# tick-wifi-mini-mk-1_1.net
KiCad netlist of a schematic drawn in EAGLE
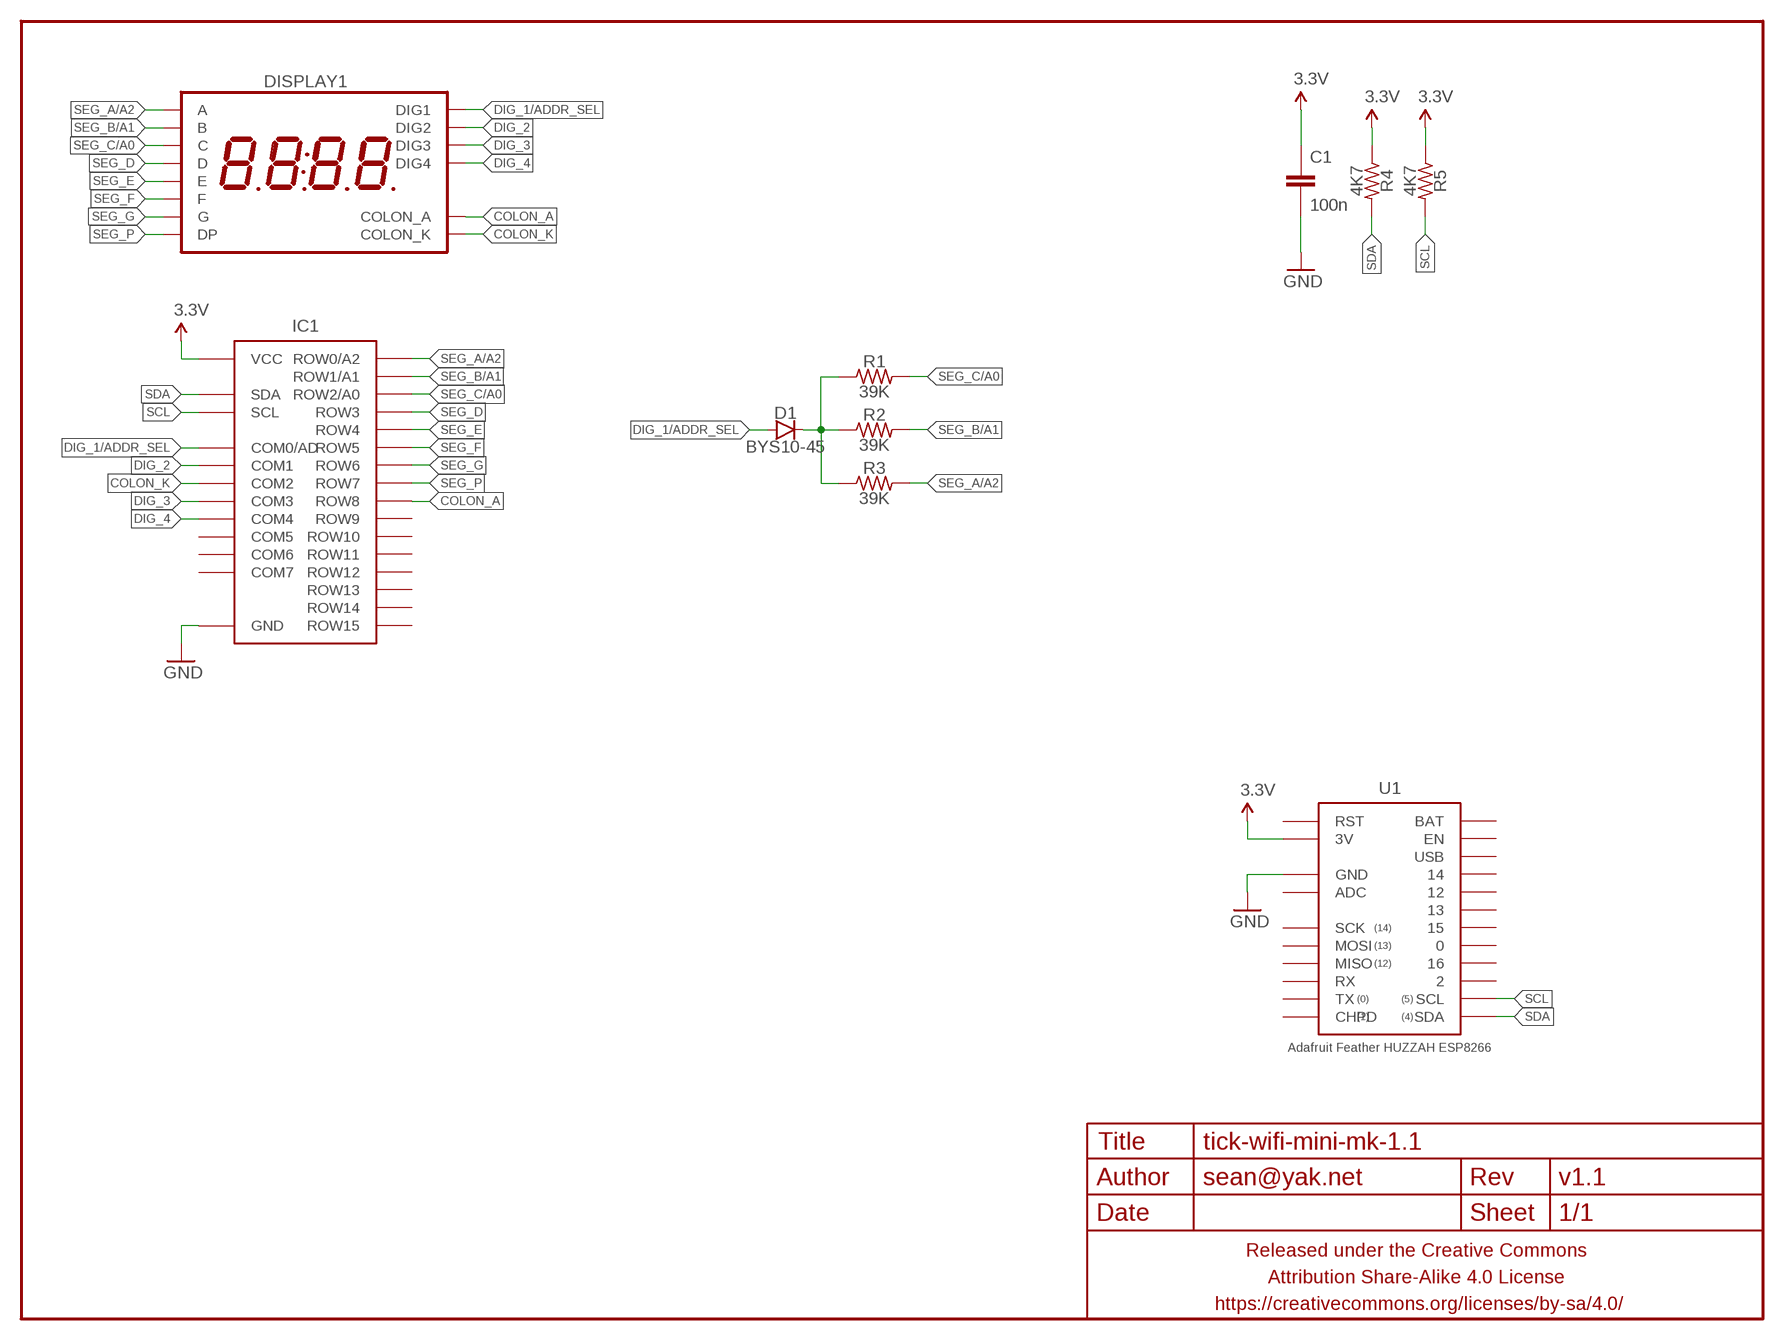
[diagram p0: schematic, sheet 1]

(export (version "E")
  (design (tool "Eeschema 10.0.6"))
  (components
    (comp (ref "C1")
      (value "100n")
      (footprint "eagle-import:C0603")
      (libsource (lib "eagle-import") (part "CAPACITOR-CERAMICC0603"))
    )
    (comp (ref "D1")
      (value "BYS10-45")
      (footprint "eagle-import:SMA-DIODE")
      (libsource (lib "eagle-import") (part "DIODESMA"))
    )
    (comp (ref "DISPLAY1")
      (value "7SEG_4DIGIT_COLON14.2MM-CC")
      (footprint "eagle-import:7SEG_4DIG_0.56IN_14MM_ADAFRUIT")
      (libsource (lib "eagle-import") (part "7SEG_4DIGIT_COLON14.2MM-CC"))
    )
    (comp (ref "FRAME1")
      (value "FRAME-LETTERNO_PACKAGE")
      (footprint "eagle-import:DUMMY")
      (fields (field (name "DESIGNER") "sean@yak.net") (field (name "VERSION") "v1.1"))
      (libsource (lib "eagle-import") (part "FRAME-LETTERNO_PACKAGE"))
    )
    (comp (ref "IC1")
      (value "HT16K33")
      (footprint "eagle-import:SOIC28W")
      (libsource (lib "eagle-import") (part "HT16K33-28SOIC28W"))
    )
    (comp (ref "R1")
      (value "39K")
      (footprint "eagle-import:R0603")
      (libsource (lib "eagle-import") (part "RESISTORR0603"))
    )
    (comp (ref "R2")
      (value "39K")
      (footprint "eagle-import:R0603")
      (libsource (lib "eagle-import") (part "RESISTORR0603"))
    )
    (comp (ref "R3")
      (value "39K")
      (footprint "eagle-import:R0603")
      (libsource (lib "eagle-import") (part "RESISTORR0603"))
    )
    (comp (ref "R4")
      (value "4K7")
      (footprint "eagle-import:R0603")
      (libsource (lib "eagle-import") (part "RESISTORR0603"))
    )
    (comp (ref "R5")
      (value "4K7")
      (footprint "eagle-import:R0603")
      (libsource (lib "eagle-import") (part "RESISTORR0603"))
    )
    (comp (ref "U1")
      (value "Adafruit Feather HUZZAH ESP8266")
      (footprint "eagle-import:ADAFRUIT_FEATHER_HUZZAH_NOSILK")
      (libsource (lib "eagle-import") (part "ADAFRUIT_FEATHER_HUZZAH_ESP8266NOSILK"))
    )
  )
  (nets
    (net (code "1") (name "3.3V") (class "Default")
      (node (ref "C1") (pin "1") (pinfunction "1_1") (pintype "passive"))
      (node (ref "IC1") (pin "28") (pinfunction "VCC_28") (pintype "bidirectional"))
      (node (ref "R4") (pin "1") (pinfunction "1_1") (pintype "passive"))
      (node (ref "R5") (pin "1") (pinfunction "1_1") (pintype "passive"))
      (node (ref "U1") (pin "3V") (pinfunction "3V_3V") (pintype "bidirectional"))
    )
    (net (code "2") (name "COLON_A") (class "Default")
      (node (ref "DISPLAY1") (pin "P$8") (pinfunction "COLON_A_P$8") (pintype "passive"))
      (node (ref "IC1") (pin "17") (pinfunction "ROW8_17") (pintype "bidirectional"))
    )
    (net (code "3") (name "COLON_K") (class "Default")
      (node (ref "DISPLAY1") (pin "P$7") (pinfunction "COLON_K_P$7") (pintype "passive"))
      (node (ref "IC1") (pin "4") (pinfunction "COM2_4") (pintype "bidirectional"))
    )
    (net (code "4") (name "DIG_1{slash}ADDR_SEL") (class "Default")
      (node (ref "D1") (pin "A") (pinfunction "A_A") (pintype "passive"))
      (node (ref "DISPLAY1") (pin "P$14") (pinfunction "DIG1_P$14") (pintype "passive"))
      (node (ref "IC1") (pin "2") (pinfunction "COM0/AD_2") (pintype "bidirectional"))
    )
    (net (code "5") (name "DIG_2") (class "Default")
      (node (ref "DISPLAY1") (pin "P$11") (pinfunction "DIG2_P$11") (pintype "passive"))
      (node (ref "IC1") (pin "3") (pinfunction "COM1_3") (pintype "bidirectional"))
    )
    (net (code "6") (name "DIG_3") (class "Default")
      (node (ref "DISPLAY1") (pin "P$10") (pinfunction "DIG3_P$10") (pintype "passive"))
      (node (ref "IC1") (pin "5") (pinfunction "COM3_5") (pintype "bidirectional"))
    )
    (net (code "7") (name "DIG_4") (class "Default")
      (node (ref "DISPLAY1") (pin "P$6") (pinfunction "DIG4_P$6") (pintype "passive"))
      (node (ref "IC1") (pin "6") (pinfunction "COM4_6") (pintype "bidirectional"))
    )
    (net (code "8") (name "GND") (class "Default")
      (node (ref "C1") (pin "2") (pinfunction "2_2") (pintype "passive"))
      (node (ref "IC1") (pin "1") (pinfunction "GND_1") (pintype "bidirectional"))
      (node (ref "U1") (pin "GND@0") (pinfunction "GND_GND@0") (pintype "bidirectional"))
    )
    (net (code "9") (name "Net-(D1-PadC)") (class "Default")
      (node (ref "D1") (pin "C") (pinfunction "C_C") (pintype "passive"))
      (node (ref "R1") (pin "1") (pinfunction "1_1") (pintype "passive"))
      (node (ref "R2") (pin "1") (pinfunction "1_1") (pintype "passive"))
      (node (ref "R3") (pin "1") (pinfunction "1_1") (pintype "passive"))
    )
    (net (code "10") (name "SCL") (class "Default")
      (node (ref "IC1") (pin "26") (pinfunction "SCL_26") (pintype "bidirectional"))
      (node (ref "R5") (pin "2") (pinfunction "2_2") (pintype "passive"))
      (node (ref "U1") (pin "SCL") (pinfunction "SCL_SCL") (pintype "bidirectional"))
    )
    (net (code "11") (name "SDA") (class "Default")
      (node (ref "IC1") (pin "27") (pinfunction "SDA_27") (pintype "bidirectional"))
      (node (ref "R4") (pin "2") (pinfunction "2_2") (pintype "passive"))
      (node (ref "U1") (pin "SDA") (pinfunction "SDA_SDA") (pintype "bidirectional"))
    )
    (net (code "12") (name "SEG_A{slash}A2") (class "Default")
      (node (ref "DISPLAY1") (pin "P$13") (pinfunction "A_P$13") (pintype "passive"))
      (node (ref "IC1") (pin "25") (pinfunction "ROW0/A2_25") (pintype "bidirectional"))
      (node (ref "R3") (pin "2") (pinfunction "2_2") (pintype "passive"))
    )
    (net (code "13") (name "SEG_B{slash}A1") (class "Default")
      (node (ref "DISPLAY1") (pin "P$9") (pinfunction "B_P$9") (pintype "passive"))
      (node (ref "IC1") (pin "24") (pinfunction "ROW1/A1_24") (pintype "bidirectional"))
      (node (ref "R2") (pin "2") (pinfunction "2_2") (pintype "passive"))
    )
    (net (code "14") (name "SEG_C{slash}A0") (class "Default")
      (node (ref "DISPLAY1") (pin "P$4") (pinfunction "C_P$4") (pintype "passive"))
      (node (ref "IC1") (pin "23") (pinfunction "ROW2/A0_23") (pintype "bidirectional"))
      (node (ref "R1") (pin "2") (pinfunction "2_2") (pintype "passive"))
    )
    (net (code "15") (name "SEG_D") (class "Default")
      (node (ref "DISPLAY1") (pin "P$2") (pinfunction "D_P$2") (pintype "passive"))
      (node (ref "IC1") (pin "22") (pinfunction "ROW3_22") (pintype "bidirectional"))
    )
    (net (code "16") (name "SEG_E") (class "Default")
      (node (ref "DISPLAY1") (pin "P$1") (pinfunction "E_P$1") (pintype "passive"))
      (node (ref "IC1") (pin "21") (pinfunction "ROW4_21") (pintype "bidirectional"))
    )
    (net (code "17") (name "SEG_F") (class "Default")
      (node (ref "DISPLAY1") (pin "P$12") (pinfunction "F_P$12") (pintype "passive"))
      (node (ref "IC1") (pin "20") (pinfunction "ROW5_20") (pintype "bidirectional"))
    )
    (net (code "18") (name "SEG_G") (class "Default")
      (node (ref "DISPLAY1") (pin "P$5") (pinfunction "G_P$5") (pintype "passive"))
      (node (ref "IC1") (pin "19") (pinfunction "ROW6_19") (pintype "bidirectional"))
    )
    (net (code "19") (name "SEG_P") (class "Default")
      (node (ref "DISPLAY1") (pin "P$3") (pinfunction "DP_P$3") (pintype "passive"))
      (node (ref "IC1") (pin "18") (pinfunction "ROW7_18") (pintype "bidirectional"))
    )
    (net (code "20") (name "unconnected-(IC1-COM5-Pad7)") (class "Default")
      (node (ref "IC1") (pin "7") (pinfunction "COM5_7") (pintype "bidirectional"))
    )
    (net (code "21") (name "unconnected-(IC1-COM6-Pad8)") (class "Default")
      (node (ref "IC1") (pin "8") (pinfunction "COM6_8") (pintype "bidirectional"))
    )
    (net (code "22") (name "unconnected-(IC1-COM7-Pad9)") (class "Default")
      (node (ref "IC1") (pin "9") (pinfunction "COM7_9") (pintype "bidirectional"))
    )
    (net (code "23") (name "unconnected-(IC1-ROW9-Pad16)") (class "Default")
      (node (ref "IC1") (pin "16") (pinfunction "ROW9_16") (pintype "bidirectional"))
    )
    (net (code "24") (name "unconnected-(IC1-ROW10-Pad15)") (class "Default")
      (node (ref "IC1") (pin "15") (pinfunction "ROW10_15") (pintype "bidirectional"))
    )
    (net (code "25") (name "unconnected-(IC1-ROW11-Pad14)") (class "Default")
      (node (ref "IC1") (pin "14") (pinfunction "ROW11_14") (pintype "bidirectional"))
    )
    (net (code "26") (name "unconnected-(IC1-ROW12-Pad13)") (class "Default")
      (node (ref "IC1") (pin "13") (pinfunction "ROW12_13") (pintype "bidirectional"))
    )
    (net (code "27") (name "unconnected-(IC1-ROW13-Pad12)") (class "Default")
      (node (ref "IC1") (pin "12") (pinfunction "ROW13_12") (pintype "bidirectional"))
    )
    (net (code "28") (name "unconnected-(IC1-ROW14-Pad11)") (class "Default")
      (node (ref "IC1") (pin "11") (pinfunction "ROW14_11") (pintype "bidirectional"))
    )
    (net (code "29") (name "unconnected-(IC1-ROW15-Pad10)") (class "Default")
      (node (ref "IC1") (pin "10") (pinfunction "ROW15_10") (pintype "bidirectional"))
    )
    (net (code "30") (name "unconnected-(U1-Pad0)") (class "Default")
      (node (ref "U1") (pin "0") (pinfunction "0_0") (pintype "bidirectional"))
    )
    (net (code "31") (name "unconnected-(U1-Pad2)") (class "Default")
      (node (ref "U1") (pin "2") (pinfunction "2_2") (pintype "bidirectional"))
    )
    (net (code "32") (name "unconnected-(U1-Pad12)") (class "Default")
      (node (ref "U1") (pin "12") (pinfunction "12_12") (pintype "bidirectional"))
    )
    (net (code "33") (name "unconnected-(U1-Pad13)") (class "Default")
      (node (ref "U1") (pin "13") (pinfunction "13_13") (pintype "bidirectional"))
    )
    (net (code "34") (name "unconnected-(U1-Pad14)") (class "Default")
      (node (ref "U1") (pin "14") (pinfunction "14_14") (pintype "bidirectional"))
    )
    (net (code "35") (name "unconnected-(U1-Pad15)") (class "Default")
      (node (ref "U1") (pin "15") (pinfunction "15_15") (pintype "bidirectional"))
    )
    (net (code "36") (name "unconnected-(U1-Pad16)") (class "Default")
      (node (ref "U1") (pin "16") (pinfunction "16_16") (pintype "bidirectional"))
    )
    (net (code "37") (name "unconnected-(U1-PadADC)") (class "Default")
      (node (ref "U1") (pin "ADC") (pinfunction "ADC_ADC") (pintype "bidirectional"))
    )
    (net (code "38") (name "unconnected-(U1-PadBAT)") (class "Default")
      (node (ref "U1") (pin "BAT") (pinfunction "BAT_BAT") (pintype "bidirectional"))
    )
    (net (code "39") (name "unconnected-(U1-PadCHPD)") (class "Default")
      (node (ref "U1") (pin "CHPD") (pinfunction "CHPD_CHPD") (pintype "bidirectional"))
    )
    (net (code "40") (name "unconnected-(U1-PadEN)") (class "Default")
      (node (ref "U1") (pin "EN") (pinfunction "EN_EN") (pintype "bidirectional"))
    )
    (net (code "41") (name "unconnected-(U1-PadMISO)") (class "Default")
      (node (ref "U1") (pin "MISO") (pinfunction "MISO_MISO") (pintype "bidirectional"))
    )
    (net (code "42") (name "unconnected-(U1-PadMOSI)") (class "Default")
      (node (ref "U1") (pin "MOSI") (pinfunction "MOSI_MOSI") (pintype "bidirectional"))
    )
    (net (code "43") (name "unconnected-(U1-PadRST)") (class "Default")
      (node (ref "U1") (pin "RST") (pinfunction "RST_RST") (pintype "bidirectional"))
    )
    (net (code "44") (name "unconnected-(U1-PadRX)") (class "Default")
      (node (ref "U1") (pin "RX") (pinfunction "RX_RX") (pintype "bidirectional"))
    )
    (net (code "45") (name "unconnected-(U1-PadSCK)") (class "Default")
      (node (ref "U1") (pin "SCK") (pinfunction "SCK_SCK") (pintype "bidirectional"))
    )
    (net (code "46") (name "unconnected-(U1-PadTX)") (class "Default")
      (node (ref "U1") (pin "TX") (pinfunction "TX_TX") (pintype "bidirectional"))
    )
    (net (code "47") (name "unconnected-(U1-PadUSB)") (class "Default")
      (node (ref "U1") (pin "USB") (pinfunction "USB_USB") (pintype "bidirectional"))
    )
  )
)
